# Digital__IO.net
KiCad netlist of a schematic drawn in Altium Designer
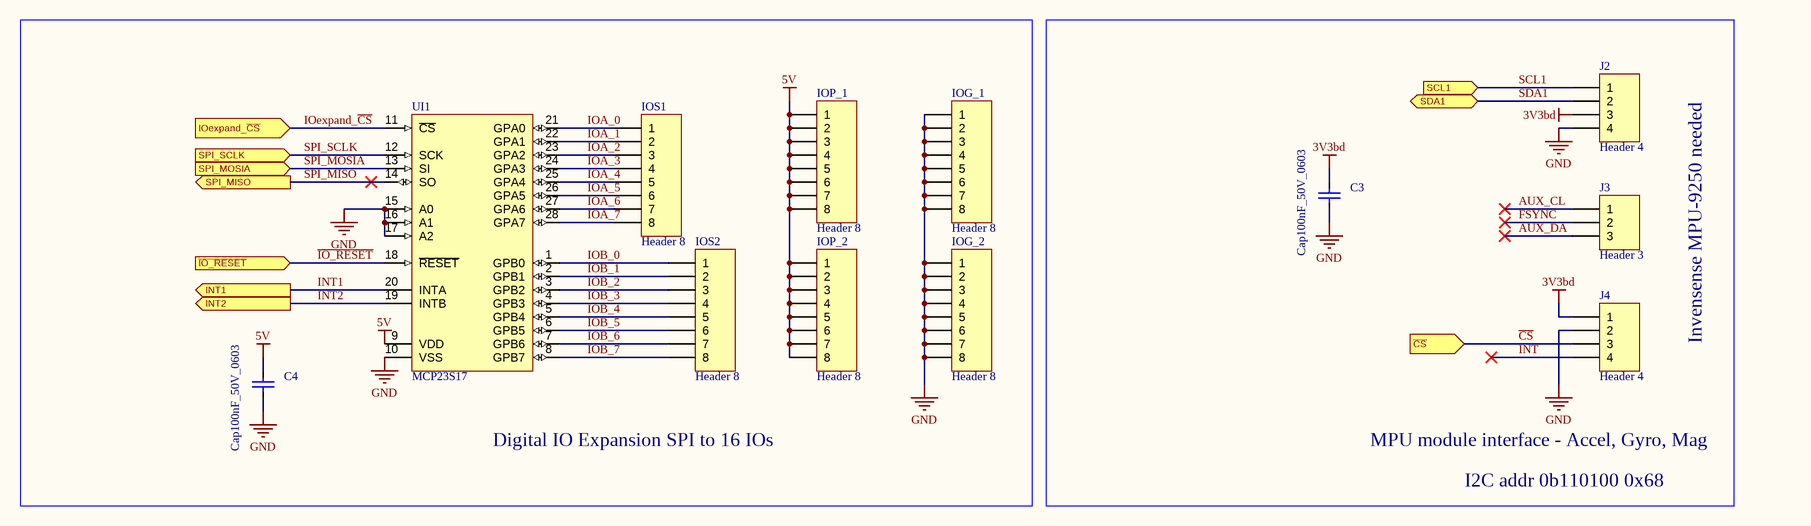
[diagram p0:  Digital_ IO.SchDoc]

(export (version "E")
  (design (tool "Eeschema 10.0.6"))
  (components
    (comp (ref "C3")
      (value "Cap100nF_50V_0603")
      (footprint "0603C_L")
      (libsource (lib " Advanced] Training Course - A365") (part "CAP General"))
    )
    (comp (ref "C4")
      (value "Cap100nF_50V_0603")
      (footprint "0603C_L")
      (libsource (lib " Advanced] Training Course - A365") (part "CAP General"))
    )
    (comp (ref "IOG_1")
      (value "Header 8")
      (footprint "HDR1X8")
      (description "Header, 8-Pin")
      (fields (field (name "PUBLISHER") "Altium Limited") (field (name "SOURCE") "WCT.SchLib"))
      (libsource (lib " Advanced] Training Course - A365") (part "Header 8"))
    )
    (comp (ref "IOG_2")
      (value "Header 8")
      (footprint "HDR1X8")
      (description "Header, 8-Pin")
      (fields (field (name "PUBLISHER") "Altium Limited") (field (name "SOURCE") "WCT.SchLib"))
      (libsource (lib " Advanced] Training Course - A365") (part "Header 8"))
    )
    (comp (ref "IOP_1")
      (value "Header 8")
      (footprint "HDR1X8")
      (description "Header, 8-Pin")
      (fields (field (name "PUBLISHER") "Altium Limited") (field (name "SOURCE") "WCT.SchLib"))
      (libsource (lib " Advanced] Training Course - A365") (part "Header 8"))
    )
    (comp (ref "IOP_2")
      (value "Header 8")
      (footprint "HDR1X8")
      (description "Header, 8-Pin")
      (fields (field (name "PUBLISHER") "Altium Limited") (field (name "SOURCE") "WCT.SchLib"))
      (libsource (lib " Advanced] Training Course - A365") (part "Header 8"))
    )
    (comp (ref "IOS1")
      (value "Header 8")
      (footprint "HDR1X8")
      (description "Header, 8-Pin")
      (fields (field (name "PUBLISHER") "Altium Limited") (field (name "SOURCE") "WCT.SchLib"))
      (libsource (lib " Advanced] Training Course - A365") (part "Header 8"))
    )
    (comp (ref "IOS2")
      (value "Header 8")
      (footprint "HDR1X8")
      (description "Header, 8-Pin")
      (fields (field (name "PUBLISHER") "Altium Limited") (field (name "SOURCE") "WCT.SchLib"))
      (libsource (lib " Advanced] Training Course - A365") (part "Header 8"))
    )
    (comp (ref "J2")
      (value "Header 4")
      (footprint "HDR1X4")
      (description "Header, 4-Pin")
      (fields (field (name "PUBLISHER") "Altium Limited") (field (name "SOURCE") "WCT.SchLib"))
      (libsource (lib " Advanced] Training Course - A365") (part "Header 4"))
    )
    (comp (ref "J3")
      (value "Header 3")
      (footprint "HDR1X3")
      (description "Header, 3-Pin")
      (fields (field (name "PUBLISHER") "Altium Limited") (field (name "SOURCE") "WCT.SchLib"))
      (libsource (lib " Advanced] Training Course - A365") (part "Header 3"))
    )
    (comp (ref "J4")
      (value "Header 4")
      (footprint "HDR1X4")
      (description "Header, 4-Pin")
      (fields (field (name "PUBLISHER") "Altium Limited") (field (name "SOURCE") "WCT.SchLib"))
      (libsource (lib " Advanced] Training Course - A365") (part "Header 4"))
    )
    (comp (ref "UI1")
      (value "MCP23S17")
      (footprint "SOIC-SO28_L")
      (description "16-Bit I/O Expander with Serial Interface, 28-Pin SOIC, Extended Temperature, Tape and Reel")
      (fields
        (field (name "MANUFACTURER") "Microchip")
        (field (name "MANUFACTURER PART NUMBER") "MCP23S17T-E/SO")
        (field (name "AVAILABLE PREVIEW IMAGES") "2D")
        (field (name "SOURCE") "WCT.SchLib")
      )
      (libsource (lib " Advanced] Training Course - A365") (part "MCP23S17"))
    )
  )
  (nets
    (net (code "1") (name "/AUX_CL") (class "Default")
      (node (ref "J3") (pin "1") (pinfunction "1_1") (pintype "passive+no_connect"))
    )
    (net (code "2") (name "/AUX_DA") (class "Default")
      (node (ref "J3") (pin "3") (pinfunction "3_3") (pintype "passive+no_connect"))
    )
    (net (code "3") (name "/FSYNC") (class "Default")
      (node (ref "J3") (pin "2") (pinfunction "2_2") (pintype "passive+no_connect"))
    )
    (net (code "4") (name "/INT") (class "Default")
      (node (ref "J4") (pin "4") (pinfunction "4_4") (pintype "passive+no_connect"))
    )
    (net (code "5") (name "/INT1") (class "Default")
      (node (ref "UI1") (pin "20") (pinfunction "INTA_20") (pintype "open_collector"))
    )
    (net (code "6") (name "/INT2") (class "Default")
      (node (ref "UI1") (pin "19") (pinfunction "INTB_19") (pintype "open_collector"))
    )
    (net (code "7") (name "/IOA_0") (class "Default")
      (node (ref "IOS1") (pin "1") (pinfunction "1_1") (pintype "passive"))
      (node (ref "UI1") (pin "21") (pinfunction "GPA0_21") (pintype "bidirectional"))
    )
    (net (code "8") (name "/IOA_1") (class "Default")
      (node (ref "IOS1") (pin "2") (pinfunction "2_2") (pintype "passive"))
      (node (ref "UI1") (pin "22") (pinfunction "GPA1_22") (pintype "bidirectional"))
    )
    (net (code "9") (name "/IOA_2") (class "Default")
      (node (ref "IOS1") (pin "3") (pinfunction "3_3") (pintype "passive"))
      (node (ref "UI1") (pin "23") (pinfunction "GPA2_23") (pintype "bidirectional"))
    )
    (net (code "10") (name "/IOA_3") (class "Default")
      (node (ref "IOS1") (pin "4") (pinfunction "4_4") (pintype "passive"))
      (node (ref "UI1") (pin "24") (pinfunction "GPA3_24") (pintype "bidirectional"))
    )
    (net (code "11") (name "/IOA_4") (class "Default")
      (node (ref "IOS1") (pin "5") (pinfunction "5_5") (pintype "passive"))
      (node (ref "UI1") (pin "25") (pinfunction "GPA4_25") (pintype "bidirectional"))
    )
    (net (code "12") (name "/IOA_5") (class "Default")
      (node (ref "IOS1") (pin "6") (pinfunction "6_6") (pintype "passive"))
      (node (ref "UI1") (pin "26") (pinfunction "GPA5_26") (pintype "bidirectional"))
    )
    (net (code "13") (name "/IOA_6") (class "Default")
      (node (ref "IOS1") (pin "7") (pinfunction "7_7") (pintype "passive"))
      (node (ref "UI1") (pin "27") (pinfunction "GPA6_27") (pintype "bidirectional"))
    )
    (net (code "14") (name "/IOA_7") (class "Default")
      (node (ref "IOS1") (pin "8") (pinfunction "8_8") (pintype "passive"))
      (node (ref "UI1") (pin "28") (pinfunction "GPA7_28") (pintype "bidirectional"))
    )
    (net (code "15") (name "/IOB_0") (class "Default")
      (node (ref "IOS2") (pin "1") (pinfunction "1_1") (pintype "passive"))
      (node (ref "UI1") (pin "1") (pinfunction "GPB0_1") (pintype "bidirectional"))
    )
    (net (code "16") (name "/IOB_1") (class "Default")
      (node (ref "IOS2") (pin "2") (pinfunction "2_2") (pintype "passive"))
      (node (ref "UI1") (pin "2") (pinfunction "GPB1_2") (pintype "bidirectional"))
    )
    (net (code "17") (name "/IOB_2") (class "Default")
      (node (ref "IOS2") (pin "3") (pinfunction "3_3") (pintype "passive"))
      (node (ref "UI1") (pin "3") (pinfunction "GPB2_3") (pintype "bidirectional"))
    )
    (net (code "18") (name "/IOB_3") (class "Default")
      (node (ref "IOS2") (pin "4") (pinfunction "4_4") (pintype "passive"))
      (node (ref "UI1") (pin "4") (pinfunction "GPB3_4") (pintype "bidirectional"))
    )
    (net (code "19") (name "/IOB_4") (class "Default")
      (node (ref "IOS2") (pin "5") (pinfunction "5_5") (pintype "passive"))
      (node (ref "UI1") (pin "5") (pinfunction "GPB4_5") (pintype "bidirectional"))
    )
    (net (code "20") (name "/IOB_5") (class "Default")
      (node (ref "IOS2") (pin "6") (pinfunction "6_6") (pintype "passive"))
      (node (ref "UI1") (pin "6") (pinfunction "GPB5_6") (pintype "bidirectional"))
    )
    (net (code "21") (name "/IOB_6") (class "Default")
      (node (ref "IOS2") (pin "7") (pinfunction "7_7") (pintype "passive"))
      (node (ref "UI1") (pin "7") (pinfunction "GPB6_7") (pintype "bidirectional"))
    )
    (net (code "22") (name "/IOB_7") (class "Default")
      (node (ref "IOS2") (pin "8") (pinfunction "8_8") (pintype "passive"))
      (node (ref "UI1") (pin "8") (pinfunction "GPB7_8") (pintype "bidirectional"))
    )
    (net (code "23") (name "/IO_RESET") (class "Default")
      (node (ref "UI1") (pin "18") (pinfunction "~{RESET}_18") (pintype "input"))
    )
    (net (code "24") (name "/IOexpand_~{CS}") (class "Default")
      (node (ref "UI1") (pin "11") (pinfunction "~{CS}_11") (pintype "input"))
    )
    (net (code "25") (name "/SCL1") (class "Default")
      (node (ref "J2") (pin "1") (pinfunction "1_1") (pintype "passive"))
    )
    (net (code "26") (name "/SDA1") (class "Default")
      (node (ref "J2") (pin "2") (pinfunction "2_2") (pintype "passive"))
    )
    (net (code "27") (name "/SPI_MISO") (class "Default")
      (node (ref "UI1") (pin "14") (pinfunction "SO_14") (pintype "bidirectional"))
    )
    (net (code "28") (name "/SPI_MOSIA") (class "Default")
      (node (ref "UI1") (pin "13") (pinfunction "SI_13") (pintype "input"))
    )
    (net (code "29") (name "/SPI_SCLK") (class "Default")
      (node (ref "UI1") (pin "12") (pinfunction "SCK_12") (pintype "input"))
    )
    (net (code "30") (name "/~{CS}") (class "Default")
      (node (ref "J4") (pin "3") (pinfunction "3_3") (pintype "passive"))
    )
    (net (code "31") (name "3V3bd") (class "Default")
      (node (ref "C3") (pin "2") (pinfunction "2_2") (pintype "passive"))
      (node (ref "J2") (pin "3") (pinfunction "3_3") (pintype "passive"))
      (node (ref "J4") (pin "1") (pinfunction "1_1") (pintype "passive"))
    )
    (net (code "32") (name "5V") (class "Default")
      (node (ref "C4") (pin "2") (pinfunction "2_2") (pintype "passive"))
      (node (ref "IOP_1") (pin "1") (pinfunction "1_1") (pintype "passive"))
      (node (ref "IOP_1") (pin "2") (pinfunction "2_2") (pintype "passive"))
      (node (ref "IOP_1") (pin "3") (pinfunction "3_3") (pintype "passive"))
      (node (ref "IOP_1") (pin "4") (pinfunction "4_4") (pintype "passive"))
      (node (ref "IOP_1") (pin "5") (pinfunction "5_5") (pintype "passive"))
      (node (ref "IOP_1") (pin "6") (pinfunction "6_6") (pintype "passive"))
      (node (ref "IOP_1") (pin "7") (pinfunction "7_7") (pintype "passive"))
      (node (ref "IOP_1") (pin "8") (pinfunction "8_8") (pintype "passive"))
      (node (ref "IOP_2") (pin "1") (pinfunction "1_1") (pintype "passive"))
      (node (ref "IOP_2") (pin "2") (pinfunction "2_2") (pintype "passive"))
      (node (ref "IOP_2") (pin "3") (pinfunction "3_3") (pintype "passive"))
      (node (ref "IOP_2") (pin "4") (pinfunction "4_4") (pintype "passive"))
      (node (ref "IOP_2") (pin "5") (pinfunction "5_5") (pintype "passive"))
      (node (ref "IOP_2") (pin "6") (pinfunction "6_6") (pintype "passive"))
      (node (ref "IOP_2") (pin "7") (pinfunction "7_7") (pintype "passive"))
      (node (ref "IOP_2") (pin "8") (pinfunction "8_8") (pintype "passive"))
      (node (ref "UI1") (pin "9") (pinfunction "VDD_9") (pintype "power_in"))
    )
    (net (code "33") (name "GND") (class "Default")
      (node (ref "C3") (pin "1") (pinfunction "1_1") (pintype "passive"))
      (node (ref "C4") (pin "1") (pinfunction "1_1") (pintype "passive"))
      (node (ref "IOG_1") (pin "1") (pinfunction "1_1") (pintype "passive"))
      (node (ref "IOG_1") (pin "2") (pinfunction "2_2") (pintype "passive"))
      (node (ref "IOG_1") (pin "3") (pinfunction "3_3") (pintype "passive"))
      (node (ref "IOG_1") (pin "4") (pinfunction "4_4") (pintype "passive"))
      (node (ref "IOG_1") (pin "5") (pinfunction "5_5") (pintype "passive"))
      (node (ref "IOG_1") (pin "6") (pinfunction "6_6") (pintype "passive"))
      (node (ref "IOG_1") (pin "7") (pinfunction "7_7") (pintype "passive"))
      (node (ref "IOG_1") (pin "8") (pinfunction "8_8") (pintype "passive"))
      (node (ref "IOG_2") (pin "1") (pinfunction "1_1") (pintype "passive"))
      (node (ref "IOG_2") (pin "2") (pinfunction "2_2") (pintype "passive"))
      (node (ref "IOG_2") (pin "3") (pinfunction "3_3") (pintype "passive"))
      (node (ref "IOG_2") (pin "4") (pinfunction "4_4") (pintype "passive"))
      (node (ref "IOG_2") (pin "5") (pinfunction "5_5") (pintype "passive"))
      (node (ref "IOG_2") (pin "6") (pinfunction "6_6") (pintype "passive"))
      (node (ref "IOG_2") (pin "7") (pinfunction "7_7") (pintype "passive"))
      (node (ref "IOG_2") (pin "8") (pinfunction "8_8") (pintype "passive"))
      (node (ref "J2") (pin "4") (pinfunction "4_4") (pintype "passive"))
      (node (ref "J4") (pin "2") (pinfunction "2_2") (pintype "passive"))
      (node (ref "UI1") (pin "10") (pinfunction "VSS_10") (pintype "power_in"))
      (node (ref "UI1") (pin "15") (pinfunction "A0_15") (pintype "input"))
      (node (ref "UI1") (pin "16") (pinfunction "A1_16") (pintype "input"))
      (node (ref "UI1") (pin "17") (pinfunction "A2_17") (pintype "input"))
    )
  )
)
